# lec-buzzer_alt.net
KiCad netlist of a schematic drawn in EAGLE
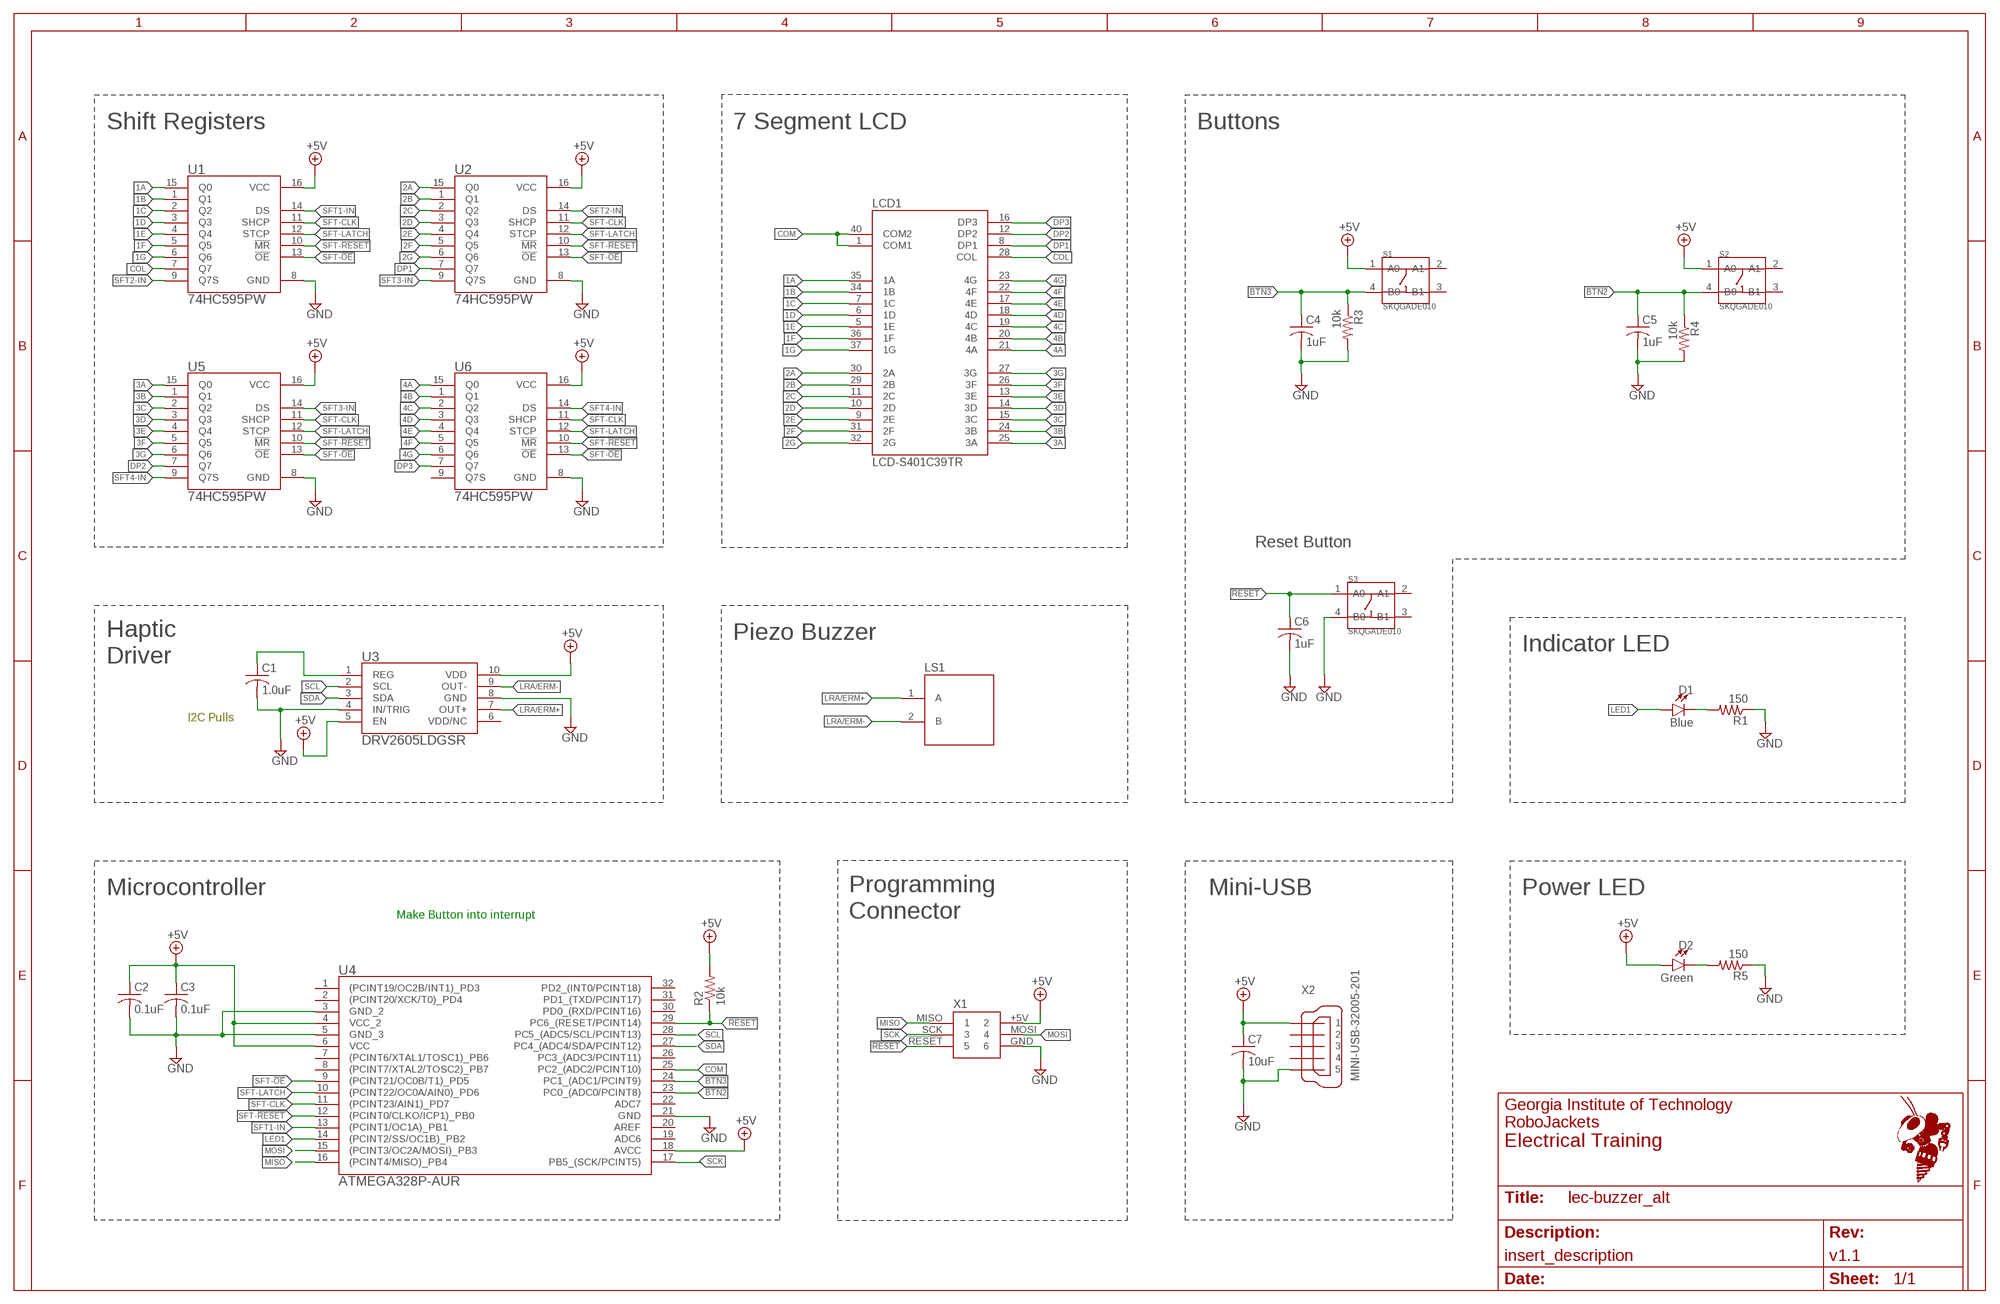
[diagram p0: schematic, sheet 1]

(export (version "E")
  (design (tool "Eeschema 10.0.6"))
  (components
    (comp (ref "C1")
      (value "1.0uF")
      (footprint "eagle-import:C0603")
      (libsource (lib "eagle-import") (part "C-USC0603"))
    )
    (comp (ref "C2")
      (value "0.1uF")
      (footprint "eagle-import:C0603")
      (libsource (lib "eagle-import") (part "C-USC0603"))
    )
    (comp (ref "C3")
      (value "0.1uF")
      (footprint "eagle-import:C0603")
      (libsource (lib "eagle-import") (part "C-USC0603"))
    )
    (comp (ref "C4")
      (value "1uF")
      (footprint "eagle-import:C0603")
      (libsource (lib "eagle-import") (part "resistor_348_C-USC0603"))
    )
    (comp (ref "C5")
      (value "1uF")
      (footprint "eagle-import:C0603")
      (libsource (lib "eagle-import") (part "resistor_348_C-USC0603"))
    )
    (comp (ref "C6")
      (value "1uF")
      (footprint "eagle-import:C0603")
      (libsource (lib "eagle-import") (part "resistor_348_C-USC0603"))
    )
    (comp (ref "C7")
      (value "10uF")
      (footprint "eagle-import:C0603")
      (libsource (lib "eagle-import") (part "C-USC0603"))
    )
    (comp (ref "D1")
      (value "Blue")
      (footprint "eagle-import:LED-0603")
      (libsource (lib "eagle-import") (part "LED-YELLOW0603"))
    )
    (comp (ref "D2")
      (value "Green")
      (footprint "eagle-import:LED-0603")
      (libsource (lib "eagle-import") (part "LED-YELLOW0603"))
    )
    (comp (ref "LCD1")
      (value "LCD-S401C39TR")
      (footprint "eagle-import:S401C39TR")
      (libsource (lib "eagle-import") (part "LCD-S401C39TR"))
    )
    (comp (ref "LS1")
      (value "PS1240P02BT")
      (footprint "eagle-import:PS1240P02BT")
      (libsource (lib "eagle-import") (part "PS1240P02BT"))
    )
    (comp (ref "R1")
      (value "150")
      (footprint "eagle-import:R0603")
      (libsource (lib "eagle-import") (part "resistor_348_R-US_R0603"))
    )
    (comp (ref "R2")
      (value "10k")
      (footprint "eagle-import:R0603")
      (libsource (lib "eagle-import") (part "R-US_R0603"))
    )
    (comp (ref "R3")
      (value "10k")
      (footprint "eagle-import:R0603")
      (libsource (lib "eagle-import") (part "resistor_348_R-US_R0603"))
    )
    (comp (ref "R4")
      (value "10k")
      (footprint "eagle-import:R0603")
      (libsource (lib "eagle-import") (part "resistor_348_R-US_R0603"))
    )
    (comp (ref "R5")
      (value "150")
      (footprint "eagle-import:R0603")
      (libsource (lib "eagle-import") (part "resistor_348_R-US_R0603"))
    )
    (comp (ref "S1")
      (value "SKQGADE010")
      (footprint "eagle-import:SW4-SMD-5.2X5.2X1.5MM")
      (libsource (lib "eagle-import") (part "SMD-SWITCH-TOP-260GF(4P-D5.2MM)"))
    )
    (comp (ref "S2")
      (value "SKQGADE010")
      (footprint "eagle-import:SW4-SMD-5.2X5.2X1.5MM")
      (libsource (lib "eagle-import") (part "SMD-SWITCH-TOP-260GF(4P-D5.2MM)"))
    )
    (comp (ref "S3")
      (value "SKQGADE010")
      (footprint "eagle-import:SW4-SMD-5.2X5.2X1.5MM")
      (libsource (lib "eagle-import") (part "SMD-SWITCH-TOP-260GF(4P-D5.2MM)"))
    )
    (comp (ref "U1")
      (value "74HC595PW")
      (footprint "eagle-import:SOT403-1")
      (libsource (lib "eagle-import") (part "74HC595PW"))
    )
    (comp (ref "U2")
      (value "74HC595PW")
      (footprint "eagle-import:SOT403-1")
      (libsource (lib "eagle-import") (part "74HC595PW"))
    )
    (comp (ref "U3")
      (value "DRV2605LDGSR")
      (footprint "eagle-import:DGS10")
      (libsource (lib "eagle-import") (part "DRV2605LDGSR"))
    )
    (comp (ref "U4")
      (value "ATMEGA328P-AUR")
      (footprint "eagle-import:ATMEGA328P-AUR")
      (libsource (lib "eagle-import") (part "ATMEGA328P-AUR"))
    )
    (comp (ref "U5")
      (value "74HC595PW")
      (footprint "eagle-import:SOT403-1")
      (libsource (lib "eagle-import") (part "74HC595PW"))
    )
    (comp (ref "U6")
      (value "74HC595PW")
      (footprint "eagle-import:SOT403-1")
      (libsource (lib "eagle-import") (part "74HC595PW"))
    )
    (comp (ref "X1")
      (value "2X3SHROUDED")
      (footprint "eagle-import:2X3SHROUDED")
      (libsource (lib "eagle-import") (part "2X3SHROUDED"))
    )
    (comp (ref "X2")
      (value "MINI-USB-32005-201")
      (footprint "eagle-import:32005-201")
      (libsource (lib "eagle-import") (part "MINI-USB-32005-201"))
    )
  )
  (nets
    (net (code "1") (name "+5V") (class "Default")
      (node (ref "C2") (pin "1") (pinfunction "1_1") (pintype "passive"))
      (node (ref "C3") (pin "1") (pinfunction "1_1") (pintype "passive"))
      (node (ref "C7") (pin "1") (pinfunction "1_1") (pintype "passive"))
      (node (ref "D2") (pin "A") (pinfunction "A_A") (pintype "passive"))
      (node (ref "R2") (pin "2") (pinfunction "2_2") (pintype "passive"))
      (node (ref "S1") (pin "1") (pinfunction "A0_1") (pintype "bidirectional"))
      (node (ref "S2") (pin "1") (pinfunction "A0_1") (pintype "bidirectional"))
      (node (ref "U1") (pin "16") (pinfunction "VCC_16") (pintype "bidirectional"))
      (node (ref "U2") (pin "16") (pinfunction "VCC_16") (pintype "bidirectional"))
      (node (ref "U3") (pin "10") (pinfunction "VDD_10") (pintype "bidirectional"))
      (node (ref "U3") (pin "5") (pinfunction "EN_5") (pintype "input"))
      (node (ref "U4") (pin "18") (pinfunction "AVCC_18") (pintype "bidirectional"))
      (node (ref "U4") (pin "4") (pinfunction "VCC_2_4") (pintype "bidirectional"))
      (node (ref "U4") (pin "6") (pinfunction "VCC_6") (pintype "bidirectional"))
      (node (ref "U5") (pin "16") (pinfunction "VCC_16") (pintype "bidirectional"))
      (node (ref "U6") (pin "16") (pinfunction "VCC_16") (pintype "bidirectional"))
      (node (ref "X1") (pin "+5V") (pinfunction "2_+5V") (pintype "bidirectional"))
      (node (ref "X2") (pin "1") (pinfunction "1_1") (pintype "passive"))
    )
    (net (code "2") (name "/SFT-~{OE}") (class "Default")
      (node (ref "U1") (pin "13") (pinfunction "~{OE}_13") (pintype "bidirectional"))
      (node (ref "U2") (pin "13") (pinfunction "~{OE}_13") (pintype "bidirectional"))
      (node (ref "U4") (pin "9") (pinfunction "(PCINT21/OC0B/T1)_PD5_9") (pintype "bidirectional"))
      (node (ref "U5") (pin "13") (pinfunction "~{OE}_13") (pintype "bidirectional"))
      (node (ref "U6") (pin "13") (pinfunction "~{OE}_13") (pintype "bidirectional"))
    )
    (net (code "3") (name "/SFT-~{RESET}") (class "Default")
      (node (ref "U1") (pin "10") (pinfunction "~{MR}_10") (pintype "bidirectional"))
      (node (ref "U2") (pin "10") (pinfunction "~{MR}_10") (pintype "bidirectional"))
      (node (ref "U4") (pin "12") (pinfunction "(PCINT0/CLKO/ICP1)_PB0_12") (pintype "bidirectional"))
      (node (ref "U5") (pin "10") (pinfunction "~{MR}_10") (pintype "bidirectional"))
      (node (ref "U6") (pin "10") (pinfunction "~{MR}_10") (pintype "bidirectional"))
    )
    (net (code "4") (name "/~{BTN2}") (class "Default")
      (node (ref "C5") (pin "1") (pinfunction "1_1") (pintype "passive"))
      (node (ref "R4") (pin "1") (pinfunction "1_1") (pintype "passive"))
      (node (ref "S2") (pin "4") (pinfunction "B0_4") (pintype "bidirectional"))
      (node (ref "U4") (pin "23") (pinfunction "PC0_(ADC0/PCINT8)_23") (pintype "bidirectional"))
    )
    (net (code "5") (name "/~{BTN3}") (class "Default")
      (node (ref "C4") (pin "1") (pinfunction "1_1") (pintype "passive"))
      (node (ref "R3") (pin "1") (pinfunction "1_1") (pintype "passive"))
      (node (ref "S1") (pin "4") (pinfunction "B0_4") (pintype "bidirectional"))
      (node (ref "U4") (pin "24") (pinfunction "PC1_(ADC1/PCINT9)_24") (pintype "bidirectional"))
    )
    (net (code "6") (name "/~{RESET}") (class "Default")
      (node (ref "C6") (pin "1") (pinfunction "1_1") (pintype "passive"))
      (node (ref "R2") (pin "1") (pinfunction "1_1") (pintype "passive"))
      (node (ref "S3") (pin "1") (pinfunction "A0_1") (pintype "bidirectional"))
      (node (ref "U4") (pin "29") (pinfunction "PC6_(RESET/PCINT14)_29") (pintype "bidirectional"))
      (node (ref "X1") (pin "!RESET") (pinfunction "5_!RESET") (pintype "bidirectional"))
    )
    (net (code "7") (name "1A") (class "Default")
      (node (ref "LCD1") (pin "35") (pinfunction "1A_35") (pintype "bidirectional"))
      (node (ref "U1") (pin "15") (pinfunction "Q0_15") (pintype "bidirectional"))
    )
    (net (code "8") (name "1B") (class "Default")
      (node (ref "LCD1") (pin "34") (pinfunction "1B_34") (pintype "bidirectional"))
      (node (ref "U1") (pin "1") (pinfunction "Q1_1") (pintype "bidirectional"))
    )
    (net (code "9") (name "1C") (class "Default")
      (node (ref "LCD1") (pin "7") (pinfunction "1C_7") (pintype "bidirectional"))
      (node (ref "U1") (pin "2") (pinfunction "Q2_2") (pintype "bidirectional"))
    )
    (net (code "10") (name "1D") (class "Default")
      (node (ref "LCD1") (pin "6") (pinfunction "1D_6") (pintype "bidirectional"))
      (node (ref "U1") (pin "3") (pinfunction "Q3_3") (pintype "bidirectional"))
    )
    (net (code "11") (name "1E") (class "Default")
      (node (ref "LCD1") (pin "5") (pinfunction "1E_5") (pintype "bidirectional"))
      (node (ref "U1") (pin "4") (pinfunction "Q4_4") (pintype "bidirectional"))
    )
    (net (code "12") (name "1F") (class "Default")
      (node (ref "LCD1") (pin "36") (pinfunction "1F_36") (pintype "bidirectional"))
      (node (ref "U1") (pin "5") (pinfunction "Q5_5") (pintype "bidirectional"))
    )
    (net (code "13") (name "1G") (class "Default")
      (node (ref "LCD1") (pin "37") (pinfunction "1G_37") (pintype "bidirectional"))
      (node (ref "U1") (pin "6") (pinfunction "Q6_6") (pintype "bidirectional"))
    )
    (net (code "14") (name "2A") (class "Default")
      (node (ref "LCD1") (pin "30") (pinfunction "2A_30") (pintype "bidirectional"))
      (node (ref "U2") (pin "15") (pinfunction "Q0_15") (pintype "bidirectional"))
    )
    (net (code "15") (name "2B") (class "Default")
      (node (ref "LCD1") (pin "29") (pinfunction "2B_29") (pintype "bidirectional"))
      (node (ref "U2") (pin "1") (pinfunction "Q1_1") (pintype "bidirectional"))
    )
    (net (code "16") (name "2C") (class "Default")
      (node (ref "LCD1") (pin "11") (pinfunction "2C_11") (pintype "bidirectional"))
      (node (ref "U2") (pin "2") (pinfunction "Q2_2") (pintype "bidirectional"))
    )
    (net (code "17") (name "2D") (class "Default")
      (node (ref "LCD1") (pin "10") (pinfunction "2D_10") (pintype "bidirectional"))
      (node (ref "U2") (pin "3") (pinfunction "Q3_3") (pintype "bidirectional"))
    )
    (net (code "18") (name "2E") (class "Default")
      (node (ref "LCD1") (pin "9") (pinfunction "2E_9") (pintype "bidirectional"))
      (node (ref "U2") (pin "4") (pinfunction "Q4_4") (pintype "bidirectional"))
    )
    (net (code "19") (name "2F") (class "Default")
      (node (ref "LCD1") (pin "31") (pinfunction "2F_31") (pintype "bidirectional"))
      (node (ref "U2") (pin "5") (pinfunction "Q5_5") (pintype "bidirectional"))
    )
    (net (code "20") (name "2G") (class "Default")
      (node (ref "LCD1") (pin "32") (pinfunction "2G_32") (pintype "bidirectional"))
      (node (ref "U2") (pin "6") (pinfunction "Q6_6") (pintype "bidirectional"))
    )
    (net (code "21") (name "3A") (class "Default")
      (node (ref "LCD1") (pin "25") (pinfunction "3A_25") (pintype "bidirectional"))
      (node (ref "U5") (pin "15") (pinfunction "Q0_15") (pintype "bidirectional"))
    )
    (net (code "22") (name "3B") (class "Default")
      (node (ref "LCD1") (pin "24") (pinfunction "3B_24") (pintype "bidirectional"))
      (node (ref "U5") (pin "1") (pinfunction "Q1_1") (pintype "bidirectional"))
    )
    (net (code "23") (name "3C") (class "Default")
      (node (ref "LCD1") (pin "15") (pinfunction "3C_15") (pintype "bidirectional"))
      (node (ref "U5") (pin "2") (pinfunction "Q2_2") (pintype "bidirectional"))
    )
    (net (code "24") (name "3D") (class "Default")
      (node (ref "LCD1") (pin "14") (pinfunction "3D_14") (pintype "bidirectional"))
      (node (ref "U5") (pin "3") (pinfunction "Q3_3") (pintype "bidirectional"))
    )
    (net (code "25") (name "3E") (class "Default")
      (node (ref "LCD1") (pin "13") (pinfunction "3E_13") (pintype "bidirectional"))
      (node (ref "U5") (pin "4") (pinfunction "Q4_4") (pintype "bidirectional"))
    )
    (net (code "26") (name "3F") (class "Default")
      (node (ref "LCD1") (pin "26") (pinfunction "3F_26") (pintype "bidirectional"))
      (node (ref "U5") (pin "5") (pinfunction "Q5_5") (pintype "bidirectional"))
    )
    (net (code "27") (name "3G") (class "Default")
      (node (ref "LCD1") (pin "27") (pinfunction "3G_27") (pintype "bidirectional"))
      (node (ref "U5") (pin "6") (pinfunction "Q6_6") (pintype "bidirectional"))
    )
    (net (code "28") (name "4A") (class "Default")
      (node (ref "LCD1") (pin "21") (pinfunction "4A_21") (pintype "bidirectional"))
      (node (ref "U6") (pin "15") (pinfunction "Q0_15") (pintype "bidirectional"))
    )
    (net (code "29") (name "4B") (class "Default")
      (node (ref "LCD1") (pin "20") (pinfunction "4B_20") (pintype "bidirectional"))
      (node (ref "U6") (pin "1") (pinfunction "Q1_1") (pintype "bidirectional"))
    )
    (net (code "30") (name "4C") (class "Default")
      (node (ref "LCD1") (pin "19") (pinfunction "4C_19") (pintype "bidirectional"))
      (node (ref "U6") (pin "2") (pinfunction "Q2_2") (pintype "bidirectional"))
    )
    (net (code "31") (name "4D") (class "Default")
      (node (ref "LCD1") (pin "18") (pinfunction "4D_18") (pintype "bidirectional"))
      (node (ref "U6") (pin "3") (pinfunction "Q3_3") (pintype "bidirectional"))
    )
    (net (code "32") (name "4E") (class "Default")
      (node (ref "LCD1") (pin "17") (pinfunction "4E_17") (pintype "bidirectional"))
      (node (ref "U6") (pin "4") (pinfunction "Q4_4") (pintype "bidirectional"))
    )
    (net (code "33") (name "4F") (class "Default")
      (node (ref "LCD1") (pin "22") (pinfunction "4F_22") (pintype "bidirectional"))
      (node (ref "U6") (pin "5") (pinfunction "Q5_5") (pintype "bidirectional"))
    )
    (net (code "34") (name "4G") (class "Default")
      (node (ref "LCD1") (pin "23") (pinfunction "4G_23") (pintype "bidirectional"))
      (node (ref "U6") (pin "6") (pinfunction "Q6_6") (pintype "bidirectional"))
    )
    (net (code "35") (name "COL") (class "Default")
      (node (ref "LCD1") (pin "28") (pinfunction "COL_28") (pintype "bidirectional"))
      (node (ref "U1") (pin "7") (pinfunction "Q7_7") (pintype "bidirectional"))
    )
    (net (code "36") (name "COM") (class "Default")
      (node (ref "LCD1") (pin "1") (pinfunction "COM1_1") (pintype "bidirectional"))
      (node (ref "LCD1") (pin "40") (pinfunction "COM2_40") (pintype "bidirectional"))
      (node (ref "U4") (pin "25") (pinfunction "PC2_(ADC2/PCINT10)_25") (pintype "bidirectional"))
    )
    (net (code "37") (name "DP1") (class "Default")
      (node (ref "LCD1") (pin "8") (pinfunction "DP1_8") (pintype "bidirectional"))
      (node (ref "U2") (pin "7") (pinfunction "Q7_7") (pintype "bidirectional"))
    )
    (net (code "38") (name "DP2") (class "Default")
      (node (ref "LCD1") (pin "12") (pinfunction "DP2_12") (pintype "bidirectional"))
      (node (ref "U5") (pin "7") (pinfunction "Q7_7") (pintype "bidirectional"))
    )
    (net (code "39") (name "DP3") (class "Default")
      (node (ref "LCD1") (pin "16") (pinfunction "DP3_16") (pintype "bidirectional"))
      (node (ref "U6") (pin "7") (pinfunction "Q7_7") (pintype "bidirectional"))
    )
    (net (code "40") (name "GND") (class "Default")
      (node (ref "C1") (pin "2") (pinfunction "2_2") (pintype "passive"))
      (node (ref "C2") (pin "2") (pinfunction "2_2") (pintype "passive"))
      (node (ref "C3") (pin "2") (pinfunction "2_2") (pintype "passive"))
      (node (ref "C4") (pin "2") (pinfunction "2_2") (pintype "passive"))
      (node (ref "C5") (pin "2") (pinfunction "2_2") (pintype "passive"))
      (node (ref "C6") (pin "2") (pinfunction "2_2") (pintype "passive"))
      (node (ref "C7") (pin "2") (pinfunction "2_2") (pintype "passive"))
      (node (ref "R1") (pin "1") (pinfunction "1_1") (pintype "passive"))
      (node (ref "R3") (pin "2") (pinfunction "2_2") (pintype "passive"))
      (node (ref "R4") (pin "2") (pinfunction "2_2") (pintype "passive"))
      (node (ref "R5") (pin "1") (pinfunction "1_1") (pintype "passive"))
      (node (ref "S3") (pin "4") (pinfunction "B0_4") (pintype "bidirectional"))
      (node (ref "U1") (pin "8") (pinfunction "GND_8") (pintype "bidirectional"))
      (node (ref "U2") (pin "8") (pinfunction "GND_8") (pintype "bidirectional"))
      (node (ref "U3") (pin "4") (pinfunction "IN/TRIG_4") (pintype "input"))
      (node (ref "U3") (pin "8") (pinfunction "GND_8") (pintype "bidirectional"))
      (node (ref "U4") (pin "21") (pinfunction "GND_21") (pintype "bidirectional"))
      (node (ref "U4") (pin "3") (pinfunction "GND_2_3") (pintype "bidirectional"))
      (node (ref "U4") (pin "5") (pinfunction "GND_3_5") (pintype "bidirectional"))
      (node (ref "U5") (pin "8") (pinfunction "GND_8") (pintype "bidirectional"))
      (node (ref "U6") (pin "8") (pinfunction "GND_8") (pintype "bidirectional"))
      (node (ref "X1") (pin "GND") (pinfunction "6_GND") (pintype "bidirectional"))
      (node (ref "X2") (pin "5") (pinfunction "5_5") (pintype "passive"))
    )
    (net (code "41") (name "LED1") (class "Default")
      (node (ref "D1") (pin "A") (pinfunction "A_A") (pintype "passive"))
      (node (ref "U4") (pin "14") (pinfunction "(PCINT2/SS/OC1B)_PB2_14") (pintype "bidirectional"))
    )
    (net (code "42") (name "LRA{slash}ERM+") (class "Default")
      (node (ref "LS1") (pin "1") (pinfunction "A_1") (pintype "bidirectional"))
      (node (ref "U3") (pin "7") (pinfunction "OUT+_7") (pintype "bidirectional"))
    )
    (net (code "43") (name "LRA{slash}ERM-") (class "Default")
      (node (ref "LS1") (pin "2") (pinfunction "B_2") (pintype "bidirectional"))
      (node (ref "U3") (pin "9") (pinfunction "OUT-_9") (pintype "bidirectional"))
    )
    (net (code "44") (name "MISO") (class "Default")
      (node (ref "U4") (pin "16") (pinfunction "(PCINT4/MISO)_PB4_16") (pintype "bidirectional"))
      (node (ref "X1") (pin "MISO") (pinfunction "1_MISO") (pintype "bidirectional"))
    )
    (net (code "45") (name "MOSI") (class "Default")
      (node (ref "U4") (pin "15") (pinfunction "(PCINT3/OC2A/MOSI)_PB3_15") (pintype "bidirectional"))
      (node (ref "X1") (pin "MOSI") (pinfunction "4_MOSI") (pintype "bidirectional"))
    )
    (net (code "46") (name "Net-(D1-PadC)") (class "Default")
      (node (ref "D1") (pin "C") (pinfunction "C_C") (pintype "passive"))
      (node (ref "R1") (pin "2") (pinfunction "2_2") (pintype "passive"))
    )
    (net (code "47") (name "Net-(D2-PadC)") (class "Default")
      (node (ref "D2") (pin "C") (pinfunction "C_C") (pintype "passive"))
      (node (ref "R5") (pin "2") (pinfunction "2_2") (pintype "passive"))
    )
    (net (code "48") (name "Net-(U3-REG)") (class "Default")
      (node (ref "C1") (pin "1") (pinfunction "1_1") (pintype "passive"))
      (node (ref "U3") (pin "1") (pinfunction "REG_1") (pintype "bidirectional"))
    )
    (net (code "49") (name "SCK") (class "Default")
      (node (ref "U4") (pin "17") (pinfunction "PB5_(SCK/PCINT5)_17") (pintype "bidirectional"))
      (node (ref "X1") (pin "SCK") (pinfunction "3_SCK") (pintype "bidirectional"))
    )
    (net (code "50") (name "SCL") (class "Default")
      (node (ref "U3") (pin "2") (pinfunction "SCL_2") (pintype "input"))
      (node (ref "U4") (pin "28") (pinfunction "PC5_(ADC5/SCL/PCINT13)_28") (pintype "bidirectional"))
    )
    (net (code "51") (name "SDA") (class "Default")
      (node (ref "U3") (pin "3") (pinfunction "SDA_3") (pintype "bidirectional"))
      (node (ref "U4") (pin "27") (pinfunction "PC4_(ADC4/SDA/PCINT12)_27") (pintype "bidirectional"))
    )
    (net (code "52") (name "SFT-CLK") (class "Default")
      (node (ref "U1") (pin "11") (pinfunction "SHCP_11") (pintype "bidirectional"))
      (node (ref "U2") (pin "11") (pinfunction "SHCP_11") (pintype "bidirectional"))
      (node (ref "U4") (pin "11") (pinfunction "(PCINT23/AIN1)_PD7_11") (pintype "bidirectional"))
      (node (ref "U5") (pin "11") (pinfunction "SHCP_11") (pintype "bidirectional"))
      (node (ref "U6") (pin "11") (pinfunction "SHCP_11") (pintype "bidirectional"))
    )
    (net (code "53") (name "SFT-LATCH") (class "Default")
      (node (ref "U1") (pin "12") (pinfunction "STCP_12") (pintype "bidirectional"))
      (node (ref "U2") (pin "12") (pinfunction "STCP_12") (pintype "bidirectional"))
      (node (ref "U4") (pin "10") (pinfunction "(PCINT22/OC0A/AIN0)_PD6_10") (pintype "bidirectional"))
      (node (ref "U5") (pin "12") (pinfunction "STCP_12") (pintype "bidirectional"))
      (node (ref "U6") (pin "12") (pinfunction "STCP_12") (pintype "bidirectional"))
    )
    (net (code "54") (name "SFT1-IN") (class "Default")
      (node (ref "U1") (pin "14") (pinfunction "DS_14") (pintype "bidirectional"))
      (node (ref "U4") (pin "13") (pinfunction "(PCINT1/OC1A)_PB1_13") (pintype "bidirectional"))
    )
    (net (code "55") (name "SFT2-IN") (class "Default")
      (node (ref "U1") (pin "9") (pinfunction "Q7S_9") (pintype "bidirectional"))
      (node (ref "U2") (pin "14") (pinfunction "DS_14") (pintype "bidirectional"))
    )
    (net (code "56") (name "SFT3-IN") (class "Default")
      (node (ref "U2") (pin "9") (pinfunction "Q7S_9") (pintype "bidirectional"))
      (node (ref "U5") (pin "14") (pinfunction "DS_14") (pintype "bidirectional"))
    )
    (net (code "57") (name "SFT4-IN") (class "Default")
      (node (ref "U5") (pin "9") (pinfunction "Q7S_9") (pintype "bidirectional"))
      (node (ref "U6") (pin "14") (pinfunction "DS_14") (pintype "bidirectional"))
    )
    (net (code "58") (name "unconnected-(S1-A1-Pad2)") (class "Default")
      (node (ref "S1") (pin "2") (pinfunction "A1_2") (pintype "bidirectional"))
    )
    (net (code "59") (name "unconnected-(S1-B1-Pad3)") (class "Default")
      (node (ref "S1") (pin "3") (pinfunction "B1_3") (pintype "bidirectional"))
    )
    (net (code "60") (name "unconnected-(S2-A1-Pad2)") (class "Default")
      (node (ref "S2") (pin "2") (pinfunction "A1_2") (pintype "bidirectional"))
    )
    (net (code "61") (name "unconnected-(S2-B1-Pad3)") (class "Default")
      (node (ref "S2") (pin "3") (pinfunction "B1_3") (pintype "bidirectional"))
    )
    (net (code "62") (name "unconnected-(S3-A1-Pad2)") (class "Default")
      (node (ref "S3") (pin "2") (pinfunction "A1_2") (pintype "bidirectional"))
    )
    (net (code "63") (name "unconnected-(S3-B1-Pad3)") (class "Default")
      (node (ref "S3") (pin "3") (pinfunction "B1_3") (pintype "bidirectional"))
    )
    (net (code "64") (name "unconnected-(U3-VDD{slash}NC-Pad6)") (class "Default")
      (node (ref "U3") (pin "6") (pinfunction "VDD/NC_6") (pintype "bidirectional"))
    )
    (net (code "65") (name "unconnected-(U4-(PCINT6{slash}XTAL1{slash}TOSC1)_PB6-Pad7)") (class "Default")
      (node (ref "U4") (pin "7") (pinfunction "(PCINT6/XTAL1/TOSC1)_PB6_7") (pintype "bidirectional"))
    )
    (net (code "66") (name "unconnected-(U4-(PCINT7{slash}XTAL2{slash}TOSC2)_PB7-Pad8)") (class "Default")
      (node (ref "U4") (pin "8") (pinfunction "(PCINT7/XTAL2/TOSC2)_PB7_8") (pintype "bidirectional"))
    )
    (net (code "67") (name "unconnected-(U4-(PCINT19{slash}OC2B{slash}INT1)_PD3-Pad1)") (class "Default")
      (node (ref "U4") (pin "1") (pinfunction "(PCINT19/OC2B/INT1)_PD3_1") (pintype "bidirectional"))
    )
    (net (code "68") (name "unconnected-(U4-(PCINT20{slash}XCK{slash}T0)_PD4-Pad2)") (class "Default")
      (node (ref "U4") (pin "2") (pinfunction "(PCINT20/XCK/T0)_PD4_2") (pintype "bidirectional"))
    )
    (net (code "69") (name "unconnected-(U4-ADC6-Pad19)") (class "Default")
      (node (ref "U4") (pin "19") (pinfunction "ADC6_19") (pintype "bidirectional"))
    )
    (net (code "70") (name "unconnected-(U4-ADC7-Pad22)") (class "Default")
      (node (ref "U4") (pin "22") (pinfunction "ADC7_22") (pintype "bidirectional"))
    )
    (net (code "71") (name "unconnected-(U4-AREF-Pad20)") (class "Default")
      (node (ref "U4") (pin "20") (pinfunction "AREF_20") (pintype "bidirectional"))
    )
    (net (code "72") (name "unconnected-(U4-PC3_(ADC3{slash}PCINT11)-Pad26)") (class "Default")
      (node (ref "U4") (pin "26") (pinfunction "PC3_(ADC3/PCINT11)_26") (pintype "bidirectional"))
    )
    (net (code "73") (name "unconnected-(U4-PD0_(RXD{slash}PCINT16)-Pad30)") (class "Default")
      (node (ref "U4") (pin "30") (pinfunction "PD0_(RXD/PCINT16)_30") (pintype "bidirectional"))
    )
    (net (code "74") (name "unconnected-(U4-PD1_(TXD{slash}PCINT17)-Pad31)") (class "Default")
      (node (ref "U4") (pin "31") (pinfunction "PD1_(TXD/PCINT17)_31") (pintype "bidirectional"))
    )
    (net (code "75") (name "unconnected-(U4-PD2_(INT0{slash}PCINT18)-Pad32)") (class "Default")
      (node (ref "U4") (pin "32") (pinfunction "PD2_(INT0/PCINT18)_32") (pintype "bidirectional"))
    )
    (net (code "76") (name "unconnected-(U6-Q7S-Pad9)") (class "Default")
      (node (ref "U6") (pin "9") (pinfunction "Q7S_9") (pintype "bidirectional"))
    )
    (net (code "77") (name "unconnected-(X2-Pad2)") (class "Default")
      (node (ref "X2") (pin "2") (pinfunction "2_2") (pintype "passive"))
    )
    (net (code "78") (name "unconnected-(X2-Pad3)") (class "Default")
      (node (ref "X2") (pin "3") (pinfunction "3_3") (pintype "passive"))
    )
    (net (code "79") (name "unconnected-(X2-Pad4)") (class "Default")
      (node (ref "X2") (pin "4") (pinfunction "4_4") (pintype "passive"))
    )
  )
)
